# Battery_Protection.net
KiCad netlist of a schematic drawn in Altium Designer
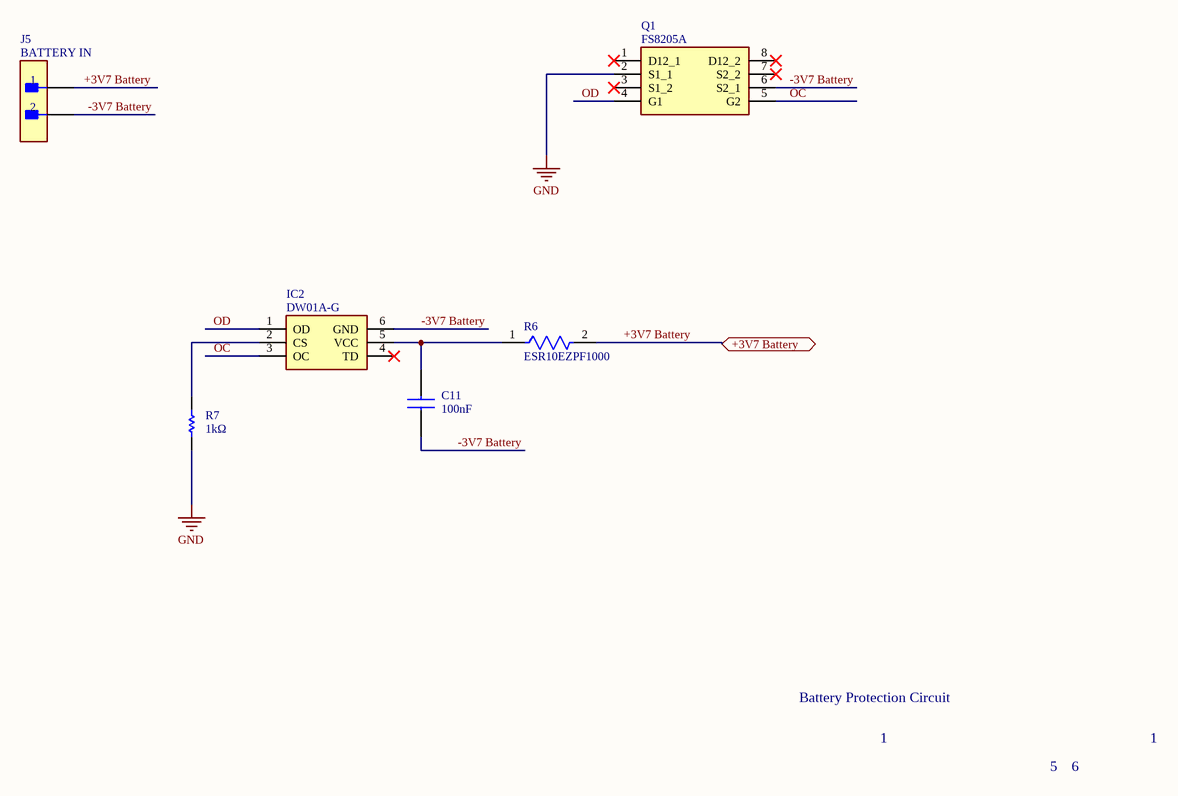
[diagram p0: Battery Protection.SchDoc]

(export (version "E")
  (design (tool "Eeschema 10.0.6"))
  (components
    (comp (ref "C11")
      (value "100nF")
      (footprint "SamacSys:CAPC2013X137N")
      (description "Capacitor")
      (fields
        (field (name "MANUFACTURER_PART_NUMBER") "0805B104K500NT")
        (field (name "MOUSER PART NUMBER") "767-0805B104K500NT")
      )
      (libsource (lib "*") (part "0805B104K500NT"))
    )
    (comp (ref "IC2")
      (value "DW01A-G")
      (footprint "SamacSys:SOT95P280X135-6N")
      (description "Integrated Circuit")
      (libsource (lib "*") (part "DW01A-G"))
    )
    (comp (ref "J5")
      (value "BATTERY IN")
      (footprint "FP-B2B-EH-A_LF_SN-MFG")
      (description "B2B-EH-A(LF)(SN), CONN HEADER VERT 2POS 2.5MM")
      (libsource (lib "Altium Content Vault") (part "3bc925449376181038e59eaffc5286c"))
    )
    (comp (ref "Q1")
      (value "FS8205A")
      (footprint "SamacSys:SOP65P640X120-8N")
      (description "MOSFET (N-Channel)")
      (libsource (lib "*") (part "FS8205A"))
    )
    (comp (ref "R6")
      (value "ESR10EZPF1000")
      (footprint "FP-ESR10-IPC_C")
      (description "100Ω ±1% 0.4W 0805 Anti-Surge Chip Resistor AEC-Q200")
      (fields (field (name "TOLERANCE") "1%"))
      (libsource (lib "Altium Content Vault") (part "1029c3af85768c4190bb7ad29bc67b5"))
    )
    (comp (ref "R7")
      (value "1kΩ")
      (footprint "RESC2013X60X30ML20T20")
      (fields (field (name "PART NUMBER") "RK73B2ATTD102J") (field (name "MANUFACTURER") "KOA Speer"))
      (libsource (lib "Altium Content Vault") (part "RES"))
    )
  )
  (nets
    (net (code "1") (name "/+3V7 Battery") (class "Default")
      (node (ref "J5") (pin "1") (pinfunction "1_1") (pintype "passive"))
      (node (ref "R6") (pin "2") (pinfunction "2_2") (pintype "passive"))
    )
    (net (code "2") (name "/-3V7 Battery") (class "Default")
      (node (ref "C11") (pin "2") (pinfunction "2_2") (pintype "passive"))
      (node (ref "IC2") (pin "6") (pinfunction "GND_6") (pintype "passive"))
      (node (ref "J5") (pin "2") (pinfunction "2_2") (pintype "passive"))
      (node (ref "Q1") (pin "6") (pinfunction "S2_1_6") (pintype "passive"))
    )
    (net (code "3") (name "/OC") (class "Default")
      (node (ref "IC2") (pin "3") (pinfunction "OC_3") (pintype "passive"))
      (node (ref "Q1") (pin "5") (pinfunction "G2_5") (pintype "passive"))
    )
    (net (code "4") (name "/OD") (class "Default")
      (node (ref "IC2") (pin "1") (pinfunction "OD_1") (pintype "passive"))
      (node (ref "Q1") (pin "4") (pinfunction "G1_4") (pintype "passive"))
    )
    (net (code "5") (name "GND") (class "Default")
      (node (ref "Q1") (pin "2") (pinfunction "S1_1_2") (pintype "passive"))
      (node (ref "R7") (pin "1") (pinfunction "1_1") (pintype "passive"))
    )
    (net (code "6") (name "Net-(IC2-CS)") (class "Default")
      (node (ref "IC2") (pin "2") (pinfunction "CS_2") (pintype "passive"))
      (node (ref "R7") (pin "2") (pinfunction "2_2") (pintype "passive"))
    )
    (net (code "7") (name "Net-(IC2-VCC)") (class "Default")
      (node (ref "C11") (pin "1") (pinfunction "1_1") (pintype "passive"))
      (node (ref "IC2") (pin "5") (pinfunction "VCC_5") (pintype "passive"))
      (node (ref "R6") (pin "1") (pinfunction "1_1") (pintype "passive"))
    )
    (net (code "8") (name "unconnected-(IC2-TD-Pad4)") (class "Default")
      (node (ref "IC2") (pin "4") (pinfunction "TD_4") (pintype "passive+no_connect"))
    )
    (net (code "9") (name "unconnected-(Q1-D12_1-Pad1)") (class "Default")
      (node (ref "Q1") (pin "1") (pinfunction "D12_1_1") (pintype "passive+no_connect"))
    )
    (net (code "10") (name "unconnected-(Q1-D12_2-Pad8)") (class "Default")
      (node (ref "Q1") (pin "8") (pinfunction "D12_2_8") (pintype "passive+no_connect"))
    )
    (net (code "11") (name "unconnected-(Q1-S1_2-Pad3)") (class "Default")
      (node (ref "Q1") (pin "3") (pinfunction "S1_2_3") (pintype "passive+no_connect"))
    )
    (net (code "12") (name "unconnected-(Q1-S2_2-Pad7)") (class "Default")
      (node (ref "Q1") (pin "7") (pinfunction "S2_2_7") (pintype "passive+no_connect"))
    )
  )
)
